# EV_SH.net
KiCad netlist of a schematic drawn in Altium Designer
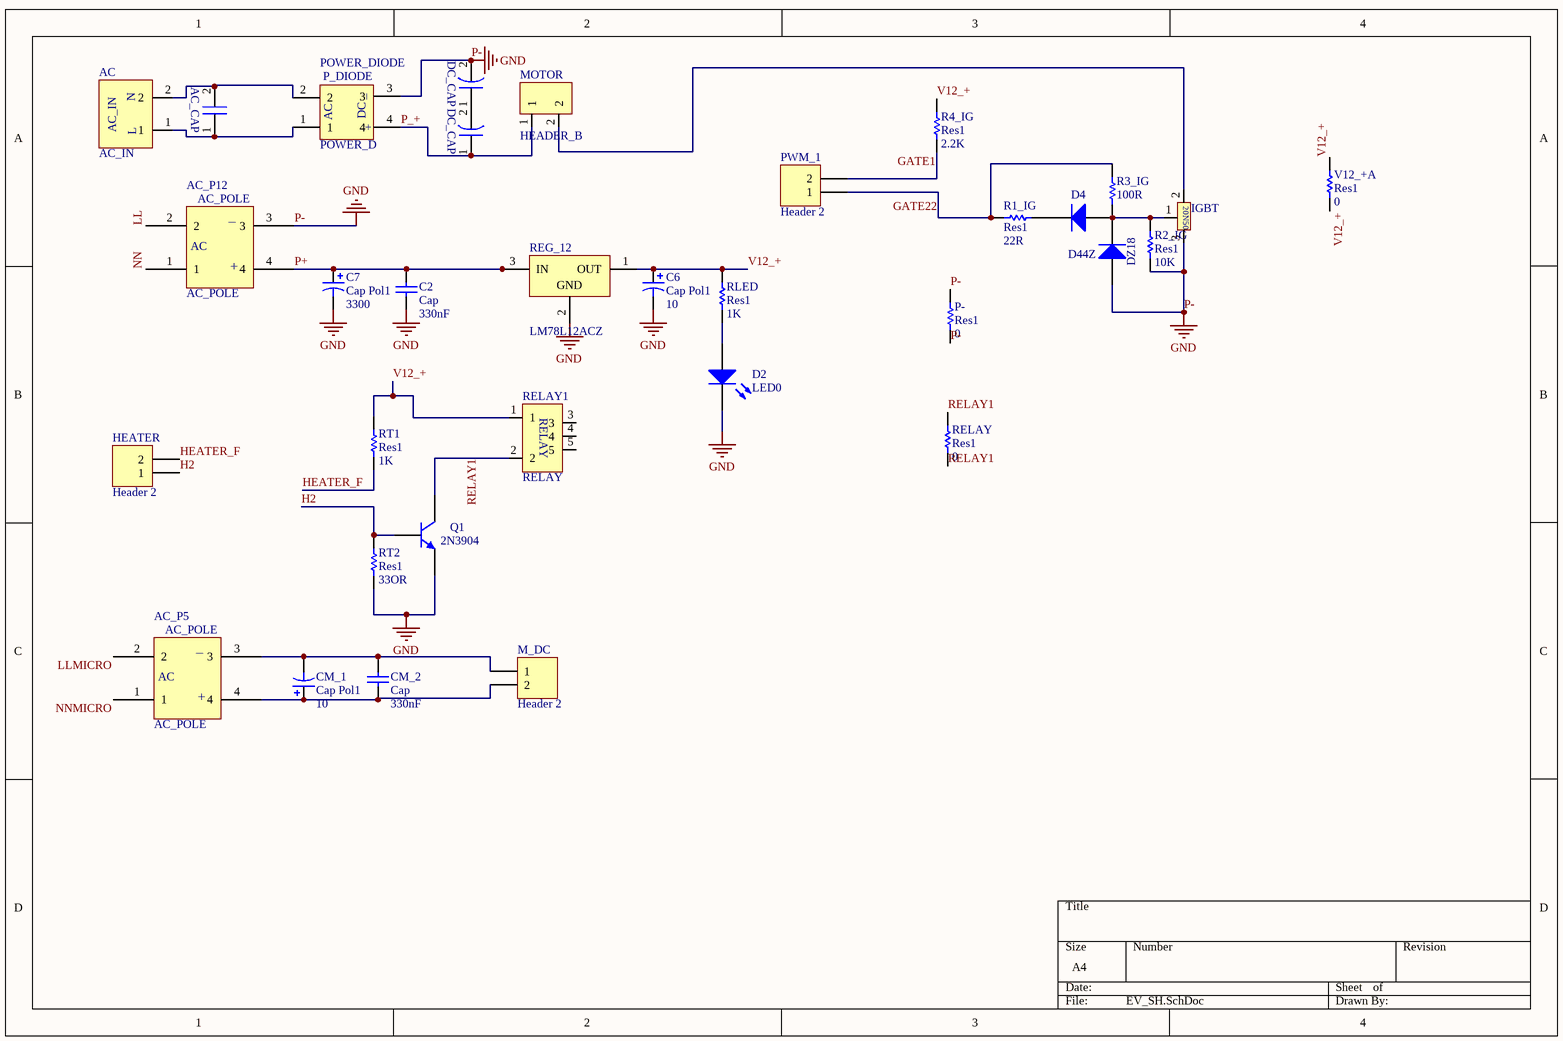
[diagram p0: EV_SH.SchDoc]

(export (version "E")
  (design (tool "Eeschema 10.0.6"))
  (components
    (comp (ref "AC") (value "AC_IN") (footprint "AC_IN") (libsource (lib "AC_IN_SH") (part "AC_IN")))
    (comp (ref "AC_C") (value "AC_CAP") (footprint "AC_CAP_P") (libsource (lib "AC_CAP_L") (part "AC_CAP")))
    (comp (ref "AC_P5") (value "AC_POLE") (footprint "AC_P") (libsource (lib "AC_POLE_SL") (part "AC_POLE")))
    (comp (ref "AC_P12") (value "AC_POLE") (footprint "AC_P") (libsource (lib "AC_POLE_SL") (part "AC_POLE")))
    (comp (ref "C2")
      (value "Cap")
      (footprint "RAD-0.1")
      (description "Capacitor")
      (fields (field (name "ALTIUM_VALUE") "330nF") (field (name "PUBLISHER") "Altium Limited"))
      (libsource (lib "Miscellaneous Devices") (part "Cap"))
    )
    (comp (ref "C6")
      (value "Cap Pol1")
      (footprint "C_+")
      (description "Polarized Capacitor (Radial)")
      (fields (field (name "ALTIUM_VALUE") "10") (field (name "PUBLISHER") "Altium Limited"))
      (libsource (lib "Miscellaneous Devices") (part "Cap Pol1"))
    )
    (comp (ref "C7")
      (value "Cap Pol1")
      (footprint "C_+")
      (description "Polarized Capacitor (Radial)")
      (fields (field (name "ALTIUM_VALUE") "3300") (field (name "PUBLISHER") "Altium Limited"))
      (libsource (lib "Miscellaneous Devices") (part "Cap Pol1"))
    )
    (comp (ref "CM_1")
      (value "Cap Pol1")
      (footprint "C_+")
      (description "Polarized Capacitor (Radial)")
      (fields (field (name "ALTIUM_VALUE") "10") (field (name "PUBLISHER") "Altium Limited"))
      (libsource (lib "Miscellaneous Devices") (part "Cap Pol1"))
    )
    (comp (ref "CM_2")
      (value "Cap")
      (footprint "RAD-0.1")
      (description "Capacitor")
      (fields (field (name "ALTIUM_VALUE") "330nF") (field (name "PUBLISHER") "Altium Limited"))
      (libsource (lib "Miscellaneous Devices") (part "Cap"))
    )
    (comp (ref "D2")
      (value "LED0")
      (footprint "LED0")
      (description "Typical INFRARED GaAs LED")
      (fields (field (name "PUBLISHER") "Altium Limited"))
      (libsource (lib "Miscellaneous Devices") (part "LED0"))
    )
    (comp (ref "D4")
      (value "Diode 1N4007")
      (footprint "DIO10.46-5.3x2.8")
      (description "1 Amp General Purpose Rectifier")
      (fields (field (name "PUBLISHER") "Altium Limited"))
      (libsource (lib "Miscellaneous Devices") (part "Diode 1N4007"))
    )
    (comp (ref "D44Z")
      (value "DZ18")
      (footprint "DIO10.46-5.3x2.8")
      (description "1 Amp General Purpose Rectifier")
      (fields (field (name "PUBLISHER") "Altium Limited"))
      (libsource (lib "Miscellaneous Devices") (part "Diode 1N4007"))
    )
    (comp (ref "DC_C") (value "DC_CAP") (footprint "DC_CAP_P") (libsource (lib "") (part "DC_CAP_1")))
    (comp (ref "DC_C2") (value "DC_CAP") (footprint "DC_CAP_P") (libsource (lib "DC_CAP_L") (part "DC_CAP")))
    (comp (ref "HEATER")
      (value "Header 2")
      (footprint "HDR1X2")
      (description "Header, 2-Pin")
      (fields (field (name "PUBLISHER") "Altium Limited"))
      (libsource (lib "Miscellaneous Connectors") (part "Header 2"))
    )
    (comp (ref "IGBT")
      (value "igbt_20n50")
      (footprint "20N50_S")
      (libsource (lib "INV_LIB_SH") (part "igbt_20n50"))
    )
    (comp (ref "MOTOR")
      (value "HEADER_B")
      (footprint "HEADER_B")
      (libsource (lib "HEADER_B") (part "HEADER_B"))
    )
    (comp (ref "M_DC")
      (value "Header 2")
      (footprint "HDR1X2")
      (description "Header, 2-Pin")
      (fields (field (name "PUBLISHER") "Altium Limited"))
      (libsource (lib "") (part "Header 2_1"))
    )
    (comp (ref "P-")
      (value "Res1")
      (footprint "AXIAL-0.3")
      (description "Resistor")
      (fields (field (name "ALTIUM_VALUE") "0") (field (name "PUBLISHER") "Altium Limited"))
      (libsource (lib "Miscellaneous Devices") (part "Res1"))
    )
    (comp (ref "POWER_DIODE")
      (value "POWER_D")
      (footprint "P_DIODE")
      (libsource (lib "P_DIODE_SH") (part "POWER_D"))
    )
    (comp (ref "PWM_1")
      (value "Header 2")
      (footprint "HDR1X2")
      (description "Header, 2-Pin")
      (fields (field (name "PUBLISHER") "Altium Limited"))
      (libsource (lib "Miscellaneous Connectors") (part "Header 2"))
    )
    (comp (ref "Q1")
      (value "2N3904")
      (footprint "BCY-W3/E4")
      (description "NPN General Purpose Amplifier")
      (fields (field (name "PUBLISHER") "Altium Limited"))
      (libsource (lib "Miscellaneous Devices") (part "2N3904"))
    )
    (comp (ref "R1_IG")
      (value "Res1")
      (footprint "AXIAL-0.3")
      (description "Resistor")
      (fields (field (name "ALTIUM_VALUE") "22R") (field (name "PUBLISHER") "Altium Limited"))
      (libsource (lib "Miscellaneous Devices") (part "Res1"))
    )
    (comp (ref "R2_IG")
      (value "Res1")
      (footprint "AXIAL-0.3")
      (description "Resistor")
      (fields (field (name "ALTIUM_VALUE") "10K") (field (name "PUBLISHER") "Altium Limited"))
      (libsource (lib "Miscellaneous Devices") (part "Res1"))
    )
    (comp (ref "R3_IG")
      (value "100R")
      (footprint "AXIAL-0.3")
      (description "Resistor")
      (fields (field (name "Comment") "Res1") (field (name "PUBLISHER") "Altium Limited"))
      (libsource (lib "Miscellaneous Devices") (part "Res1"))
    )
    (comp (ref "R4_IG")
      (value "Res1")
      (footprint "AXIAL-0.3")
      (description "Resistor")
      (fields (field (name "ALTIUM_VALUE") "2.2K") (field (name "PUBLISHER") "Altium Limited"))
      (libsource (lib "Miscellaneous Devices") (part "Res1"))
    )
    (comp (ref "REG_12")
      (value "LM78L12ACZ")
      (footprint "T03B")
      (description "3-Terminal Positive Regulators")
      (fields
        (field (name "MANUFACTURER") "National Semiconductor")
        (field (name "DIGIKEYPARTNUMBER") "LM78L12ACZ-ND")
        (field (name "PUBLISHER") "Altium Limited")
      )
      (libsource (lib "NSC LDO") (part "LM78L12ACZ"))
    )
    (comp (ref "RELAY")
      (value "Res1")
      (footprint "AXIAL-0.3")
      (description "Resistor")
      (fields (field (name "ALTIUM_VALUE") "0") (field (name "PUBLISHER") "Altium Limited"))
      (libsource (lib "Miscellaneous Devices") (part "Res1"))
    )
    (comp (ref "RELAY1") (value "RELAY") (footprint "RELAY_OK") (libsource (lib "RELAY_SH") (part "RELAY")))
    (comp (ref "RLED")
      (value "Res1")
      (footprint "AXIAL-0.3")
      (description "Resistor")
      (fields (field (name "ALTIUM_VALUE") "1K") (field (name "PUBLISHER") "Altium Limited"))
      (libsource (lib "Miscellaneous Devices") (part "Res1"))
    )
    (comp (ref "RT1")
      (value "Res1")
      (footprint "AXIAL-0.3")
      (description "Resistor")
      (fields (field (name "ALTIUM_VALUE") "1K") (field (name "PUBLISHER") "Altium Limited"))
      (libsource (lib "Miscellaneous Devices") (part "Res1"))
    )
    (comp (ref "RT2")
      (value "Res1")
      (footprint "AXIAL-0.3")
      (description "Resistor")
      (fields (field (name "ALTIUM_VALUE") "33OR") (field (name "PUBLISHER") "Altium Limited"))
      (libsource (lib "Miscellaneous Devices") (part "Res1"))
    )
    (comp (ref "V12_+A")
      (value "Res1")
      (footprint "AXIAL-0.3")
      (description "Resistor")
      (fields (field (name "ALTIUM_VALUE") "0") (field (name "PUBLISHER") "Altium Limited"))
      (libsource (lib "Miscellaneous Devices") (part "Res1"))
    )
  )
  (nets
    (net (code "1") (name "/GATE1") (class "Default")
      (node (ref "PWM_1") (pin "2") (pinfunction "2_2") (pintype "passive"))
      (node (ref "R4_IG") (pin "2") (pinfunction "2_2") (pintype "passive"))
    )
    (net (code "2") (name "/GATE22") (class "Default")
      (node (ref "PWM_1") (pin "1") (pinfunction "1_1") (pintype "passive"))
      (node (ref "R1_IG") (pin "2") (pinfunction "2_2") (pintype "passive"))
      (node (ref "R3_IG") (pin "1") (pinfunction "1_1") (pintype "passive"))
    )
    (net (code "3") (name "/H2") (class "Default")
      (node (ref "HEATER") (pin "1") (pinfunction "1_1") (pintype "passive"))
      (node (ref "Q1") (pin "2") (pinfunction "B_2") (pintype "passive"))
      (node (ref "RT2") (pin "1") (pinfunction "1_1") (pintype "passive"))
    )
    (net (code "4") (name "/HEATER_F") (class "Default")
      (node (ref "HEATER") (pin "2") (pinfunction "2_2") (pintype "passive"))
      (node (ref "RT1") (pin "2") (pinfunction "2_2") (pintype "passive"))
    )
    (net (code "5") (name "/LL") (class "Default")
      (node (ref "AC_P12") (pin "2") (pinfunction "2_2") (pintype "passive"))
    )
    (net (code "6") (name "/LLMICRO") (class "Default")
      (node (ref "AC_P5") (pin "2") (pinfunction "2_2") (pintype "passive"))
    )
    (net (code "7") (name "/NN") (class "Default")
      (node (ref "AC_P12") (pin "1") (pinfunction "1_1") (pintype "passive"))
    )
    (net (code "8") (name "/NNMICRO") (class "Default")
      (node (ref "AC_P5") (pin "1") (pinfunction "1_1") (pintype "passive"))
    )
    (net (code "9") (name "/P+") (class "Default")
      (node (ref "AC_P12") (pin "4") (pinfunction "4_4") (pintype "passive"))
      (node (ref "C2") (pin "2") (pinfunction "2_2") (pintype "passive"))
      (node (ref "C7") (pin "1") (pinfunction "1_1") (pintype "passive"))
      (node (ref "REG_12") (pin "3") (pinfunction "IN_3") (pintype "power_in"))
    )
    (net (code "10") (name "/P_+") (class "Default")
      (node (ref "DC_C") (pin "1") (pinfunction "1_1") (pintype "passive"))
      (node (ref "MOTOR") (pin "1") (pinfunction "1_1") (pintype "passive"))
      (node (ref "POWER_DIODE") (pin "4") (pinfunction "4_4") (pintype "passive"))
    )
    (net (code "11") (name "/RELAY1") (class "Default")
      (node (ref "Q1") (pin "3") (pinfunction "C_3") (pintype "passive"))
      (node (ref "RELAY") (pin "1") (pinfunction "1_1") (pintype "passive"))
      (node (ref "RELAY") (pin "2") (pinfunction "2_2") (pintype "passive"))
      (node (ref "RELAY1") (pin "2") (pinfunction "2_2") (pintype "passive"))
    )
    (net (code "12") (name "/V12_+") (class "Default")
      (node (ref "C6") (pin "1") (pinfunction "1_1") (pintype "passive"))
      (node (ref "R4_IG") (pin "1") (pinfunction "1_1") (pintype "passive"))
      (node (ref "REG_12") (pin "1") (pinfunction "OUT_1") (pintype "power_in"))
      (node (ref "RELAY1") (pin "1") (pinfunction "1_1") (pintype "passive"))
      (node (ref "RLED") (pin "2") (pinfunction "2_2") (pintype "passive"))
      (node (ref "RT1") (pin "1") (pinfunction "1_1") (pintype "passive"))
      (node (ref "V12_+A") (pin "1") (pinfunction "1_1") (pintype "passive"))
      (node (ref "V12_+A") (pin "2") (pinfunction "2_2") (pintype "passive"))
    )
    (net (code "13") (name "GND") (class "Default")
      (node (ref "AC_P12") (pin "3") (pinfunction "3_3") (pintype "passive"))
      (node (ref "C2") (pin "1") (pinfunction "1_1") (pintype "passive"))
      (node (ref "C6") (pin "2") (pinfunction "2_2") (pintype "passive"))
      (node (ref "C7") (pin "2") (pinfunction "2_2") (pintype "passive"))
      (node (ref "D2") (pin "2") (pinfunction "K_2") (pintype "passive"))
      (node (ref "D44Z") (pin "1") (pinfunction "A_1") (pintype "passive"))
      (node (ref "DC_C2") (pin "2") (pinfunction "2_2") (pintype "passive"))
      (node (ref "IGBT") (pin "3") (pinfunction "E_3") (pintype "passive"))
      (node (ref "P-") (pin "1") (pinfunction "1_1") (pintype "passive"))
      (node (ref "P-") (pin "2") (pinfunction "2_2") (pintype "passive"))
      (node (ref "POWER_DIODE") (pin "3") (pinfunction "3_3") (pintype "passive"))
      (node (ref "Q1") (pin "1") (pinfunction "E_1") (pintype "passive"))
      (node (ref "R2_IG") (pin "1") (pinfunction "1_1") (pintype "passive"))
      (node (ref "REG_12") (pin "2") (pinfunction "GND_2") (pintype "power_in"))
      (node (ref "RT2") (pin "2") (pinfunction "2_2") (pintype "passive"))
    )
    (net (code "14") (name "Net-(AC-Pad1)") (class "Default")
      (node (ref "AC") (pin "1") (pinfunction "1_1") (pintype "passive"))
      (node (ref "AC_C") (pin "1") (pinfunction "1_1") (pintype "passive"))
      (node (ref "POWER_DIODE") (pin "1") (pinfunction "1_1") (pintype "passive"))
    )
    (net (code "15") (name "Net-(AC-Pad2)") (class "Default")
      (node (ref "AC") (pin "2") (pinfunction "2_2") (pintype "passive"))
      (node (ref "AC_C") (pin "2") (pinfunction "2_2") (pintype "passive"))
      (node (ref "POWER_DIODE") (pin "2") (pinfunction "2_2") (pintype "passive"))
    )
    (net (code "16") (name "Net-(AC_P5-Pad3)") (class "Default")
      (node (ref "AC_P5") (pin "3") (pinfunction "3_3") (pintype "passive"))
      (node (ref "CM_1") (pin "2") (pinfunction "2_2") (pintype "passive"))
      (node (ref "CM_2") (pin "2") (pinfunction "2_2") (pintype "passive"))
      (node (ref "M_DC") (pin "1") (pinfunction "1_1") (pintype "passive"))
    )
    (net (code "17") (name "Net-(AC_P5-Pad4)") (class "Default")
      (node (ref "AC_P5") (pin "4") (pinfunction "4_4") (pintype "passive"))
      (node (ref "CM_1") (pin "1") (pinfunction "1_1") (pintype "passive"))
      (node (ref "CM_2") (pin "1") (pinfunction "1_1") (pintype "passive"))
      (node (ref "M_DC") (pin "2") (pinfunction "2_2") (pintype "passive"))
    )
    (net (code "18") (name "Net-(D2-A)") (class "Default")
      (node (ref "D2") (pin "1") (pinfunction "A_1") (pintype "passive"))
      (node (ref "RLED") (pin "1") (pinfunction "1_1") (pintype "passive"))
    )
    (net (code "19") (name "Net-(D4-A)") (class "Default")
      (node (ref "D4") (pin "1") (pinfunction "A_1") (pintype "passive"))
      (node (ref "D44Z") (pin "2") (pinfunction "K_2") (pintype "passive"))
      (node (ref "IGBT") (pin "1") (pinfunction "G_1") (pintype "passive"))
      (node (ref "R2_IG") (pin "2") (pinfunction "2_2") (pintype "passive"))
      (node (ref "R3_IG") (pin "2") (pinfunction "2_2") (pintype "passive"))
    )
    (net (code "20") (name "Net-(D4-K)") (class "Default")
      (node (ref "D4") (pin "2") (pinfunction "K_2") (pintype "passive"))
      (node (ref "R1_IG") (pin "1") (pinfunction "1_1") (pintype "passive"))
    )
    (net (code "21") (name "Net-(DC_C-Pad2)") (class "Default")
      (node (ref "DC_C") (pin "2") (pinfunction "2_2") (pintype "passive"))
      (node (ref "DC_C2") (pin "1") (pinfunction "1_1") (pintype "passive"))
    )
    (net (code "22") (name "Net-(IGBT-C)") (class "Default")
      (node (ref "IGBT") (pin "2") (pinfunction "C_2") (pintype "passive"))
      (node (ref "MOTOR") (pin "2") (pinfunction "2_2") (pintype "passive"))
    )
    (net (code "23") (name "unconnected-(RELAY1-Pad3)") (class "Default")
      (node (ref "RELAY1") (pin "3") (pinfunction "3_3") (pintype "passive"))
    )
    (net (code "24") (name "unconnected-(RELAY1-Pad4)") (class "Default")
      (node (ref "RELAY1") (pin "4") (pinfunction "4_4") (pintype "passive"))
    )
    (net (code "25") (name "unconnected-(RELAY1-Pad5)") (class "Default")
      (node (ref "RELAY1") (pin "5") (pinfunction "5_5") (pintype "passive"))
    )
  )
)
